# esp8266-01_carrier.net
KiCad netlist of a schematic drawn in EAGLE
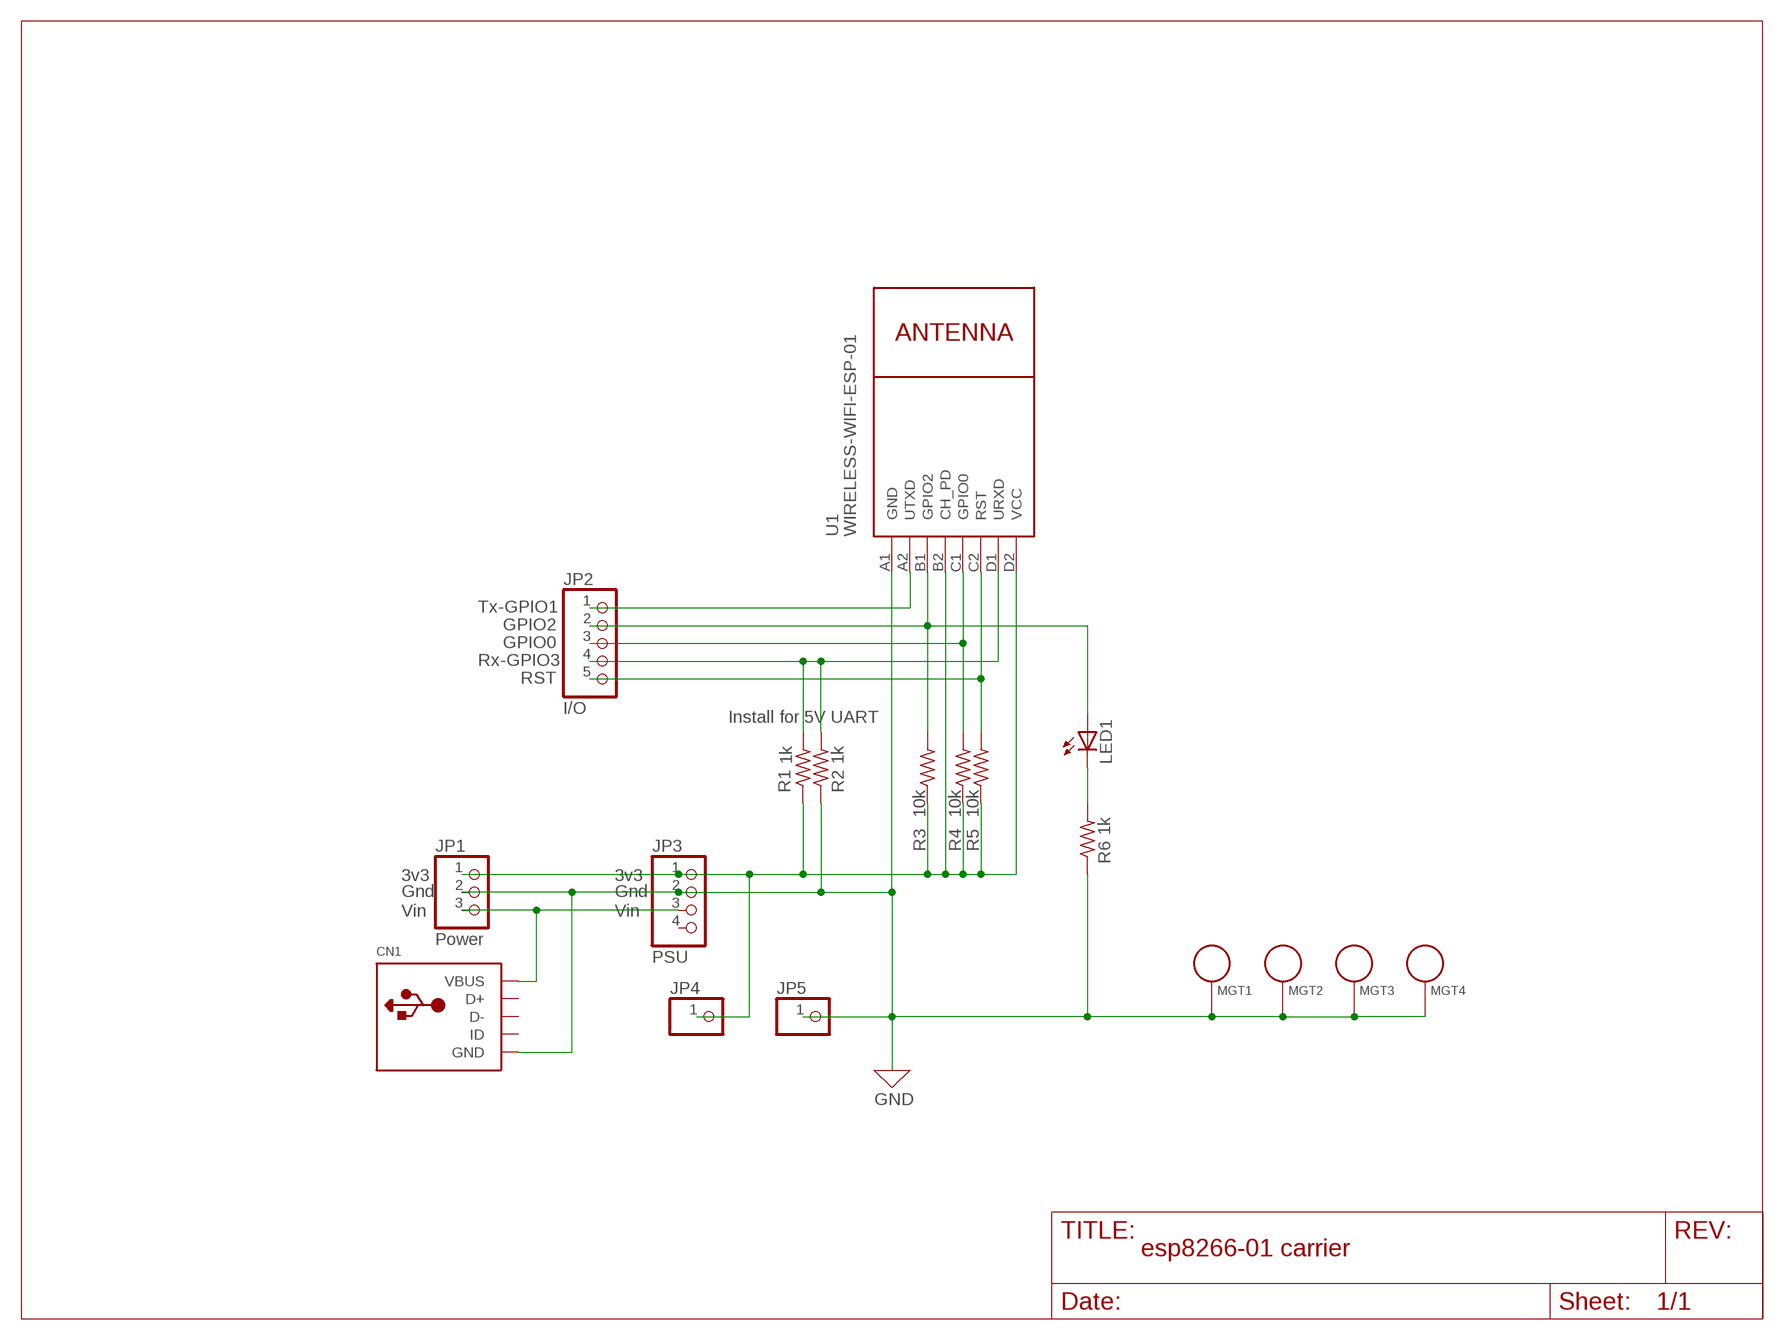
[diagram p0: schematic, sheet 1]

(export (version "E")
  (design (tool "Eeschema 10.0.6"))
  (components
    (comp (ref "CN1")
      (value "USBTHM")
      (footprint "eagle-import:USB-MINIB-THM")
      (libsource (lib "eagle-import") (part "USBTHM"))
    )
    (comp (ref "JP1")
      (value "Power")
      (footprint "eagle-import:1X03")
      (libsource (lib "eagle-import") (part "PINHD-1X3"))
    )
    (comp (ref "JP2")
      (value "I/O")
      (footprint "eagle-import:1X05")
      (libsource (lib "eagle-import") (part "PINHD-1X5"))
    )
    (comp (ref "JP3")
      (value "PSU")
      (footprint "eagle-import:1X04")
      (libsource (lib "eagle-import") (part "PINHD-1X4"))
    )
    (comp (ref "JP4")
      (value "PINHD-1X1")
      (footprint "eagle-import:1X01")
      (libsource (lib "eagle-import") (part "PINHD-1X1"))
    )
    (comp (ref "JP5")
      (value "PINHD-1X1")
      (footprint "eagle-import:1X01")
      (libsource (lib "eagle-import") (part "PINHD-1X1"))
    )
    (comp (ref "LED1")
      (value "LED5MM")
      (footprint "eagle-import:LED5MM")
      (libsource (lib "eagle-import") (part "LED5MM"))
    )
    (comp (ref "MGT1")
      (value "BEAGLEBONEBLACK_MOUNTING_HOLE")
      (footprint "eagle-import:BEAGLEBONEBLACK_MOUNTING_HOLE")
      (libsource (lib "eagle-import") (part "BEAGLEBONEBLACK_MOUNTING_HOLE"))
    )
    (comp (ref "MGT2")
      (value "BEAGLEBONEBLACK_MOUNTING_HOLE")
      (footprint "eagle-import:BEAGLEBONEBLACK_MOUNTING_HOLE")
      (libsource (lib "eagle-import") (part "BEAGLEBONEBLACK_MOUNTING_HOLE"))
    )
    (comp (ref "MGT3")
      (value "BEAGLEBONEBLACK_MOUNTING_HOLE")
      (footprint "eagle-import:BEAGLEBONEBLACK_MOUNTING_HOLE")
      (libsource (lib "eagle-import") (part "BEAGLEBONEBLACK_MOUNTING_HOLE"))
    )
    (comp (ref "MGT4")
      (value "BEAGLEBONEBLACK_MOUNTING_HOLE")
      (footprint "eagle-import:BEAGLEBONEBLACK_MOUNTING_HOLE")
      (libsource (lib "eagle-import") (part "BEAGLEBONEBLACK_MOUNTING_HOLE"))
    )
    (comp (ref "R1")
      (value "1k")
      (footprint "eagle-import:0207_10")
      (libsource (lib "eagle-import") (part "R-US_0207/10"))
    )
    (comp (ref "R2")
      (value "1k")
      (footprint "eagle-import:0207_10")
      (libsource (lib "eagle-import") (part "R-US_0207/10"))
    )
    (comp (ref "R3")
      (value "10k")
      (footprint "eagle-import:0207_10")
      (libsource (lib "eagle-import") (part "R-US_0207/10"))
    )
    (comp (ref "R4")
      (value "10k")
      (footprint "eagle-import:0207_10")
      (libsource (lib "eagle-import") (part "R-US_0207/10"))
    )
    (comp (ref "R5")
      (value "10k")
      (footprint "eagle-import:0207_10")
      (libsource (lib "eagle-import") (part "R-US_0207/10"))
    )
    (comp (ref "R6")
      (value "1k")
      (footprint "eagle-import:0207_10")
      (libsource (lib "eagle-import") (part "R-US_0207/10"))
    )
    (comp (ref "U1")
      (value "WIRELESS-WIFI-ESP-01")
      (footprint "eagle-import:WIRELESS-WIFI-ESP-01")
      (libsource (lib "eagle-import") (part "WIRELESS-WIFI-ESP-01"))
    )
  )
  (nets
    (net (code "1") (name "GND") (class "Default")
      (node (ref "CN1") (pin "GND") (pinfunction "GND_GND") (pintype "power_in"))
      (node (ref "JP1") (pin "2") (pinfunction "2_2") (pintype "passive"))
      (node (ref "JP3") (pin "2") (pinfunction "2_2") (pintype "passive"))
      (node (ref "JP5") (pin "1") (pinfunction "1_1") (pintype "passive"))
      (node (ref "MGT1") (pin "P$1") (pinfunction "P$1_P$1") (pintype "bidirectional"))
      (node (ref "MGT2") (pin "P$1") (pinfunction "P$1_P$1") (pintype "bidirectional"))
      (node (ref "MGT3") (pin "P$1") (pinfunction "P$1_P$1") (pintype "bidirectional"))
      (node (ref "MGT4") (pin "P$1") (pinfunction "P$1_P$1") (pintype "bidirectional"))
      (node (ref "R2") (pin "1") (pinfunction "1_1") (pintype "passive"))
      (node (ref "R6") (pin "1") (pinfunction "1_1") (pintype "passive"))
      (node (ref "U1") (pin "A1") (pinfunction "GND_A1") (pintype "power_in"))
    )
    (net (code "2") (name "Net-(CN1-PadVBUS)") (class "Default")
      (node (ref "CN1") (pin "VBUS") (pinfunction "VBUS_VBUS") (pintype "power_in"))
      (node (ref "JP1") (pin "3") (pinfunction "3_3") (pintype "passive"))
      (node (ref "JP3") (pin "3") (pinfunction "3_3") (pintype "passive"))
    )
    (net (code "3") (name "Net-(LED1-C)") (class "Default")
      (node (ref "LED1") (pin "K") (pinfunction "C_K") (pintype "passive"))
      (node (ref "R6") (pin "2") (pinfunction "2_2") (pintype "passive"))
    )
    (net (code "4") (name "Net-(U1-CH_PD)") (class "Default")
      (node (ref "JP1") (pin "1") (pinfunction "1_1") (pintype "passive"))
      (node (ref "JP3") (pin "1") (pinfunction "1_1") (pintype "passive"))
      (node (ref "JP4") (pin "1") (pinfunction "1_1") (pintype "passive"))
      (node (ref "R1") (pin "1") (pinfunction "1_1") (pintype "passive"))
      (node (ref "R3") (pin "1") (pinfunction "1_1") (pintype "passive"))
      (node (ref "R4") (pin "1") (pinfunction "1_1") (pintype "passive"))
      (node (ref "R5") (pin "1") (pinfunction "1_1") (pintype "passive"))
      (node (ref "U1") (pin "B2") (pinfunction "CH_PD_B2") (pintype "bidirectional"))
      (node (ref "U1") (pin "D2") (pinfunction "VCC_D2") (pintype "power_in"))
    )
    (net (code "5") (name "Net-(U1-GPIO0)") (class "Default")
      (node (ref "JP2") (pin "3") (pinfunction "3_3") (pintype "passive"))
      (node (ref "R4") (pin "2") (pinfunction "2_2") (pintype "passive"))
      (node (ref "U1") (pin "C1") (pinfunction "GPIO0_C1") (pintype "bidirectional"))
    )
    (net (code "6") (name "Net-(U1-GPIO2)") (class "Default")
      (node (ref "JP2") (pin "2") (pinfunction "2_2") (pintype "passive"))
      (node (ref "LED1") (pin "A") (pinfunction "A_A") (pintype "passive"))
      (node (ref "R3") (pin "2") (pinfunction "2_2") (pintype "passive"))
      (node (ref "U1") (pin "B1") (pinfunction "GPIO2_B1") (pintype "bidirectional"))
    )
    (net (code "7") (name "Net-(U1-RST)") (class "Default")
      (node (ref "JP2") (pin "5") (pinfunction "5_5") (pintype "passive"))
      (node (ref "R5") (pin "2") (pinfunction "2_2") (pintype "passive"))
      (node (ref "U1") (pin "C2") (pinfunction "RST_C2") (pintype "bidirectional"))
    )
    (net (code "8") (name "Net-(U1-URXD)") (class "Default")
      (node (ref "JP2") (pin "4") (pinfunction "4_4") (pintype "passive"))
      (node (ref "R1") (pin "2") (pinfunction "2_2") (pintype "passive"))
      (node (ref "R2") (pin "2") (pinfunction "2_2") (pintype "passive"))
      (node (ref "U1") (pin "D1") (pinfunction "URXD_D1") (pintype "bidirectional"))
    )
    (net (code "9") (name "Net-(U1-UTXD)") (class "Default")
      (node (ref "JP2") (pin "1") (pinfunction "1_1") (pintype "passive"))
      (node (ref "U1") (pin "A2") (pinfunction "UTXD_A2") (pintype "bidirectional"))
    )
    (net (code "10") (name "unconnected-(CN1-PadD+)") (class "Default")
      (node (ref "CN1") (pin "D+") (pinfunction "D+_D+") (pintype "bidirectional"))
    )
    (net (code "11") (name "unconnected-(CN1-PadD-)") (class "Default")
      (node (ref "CN1") (pin "D-") (pinfunction "D-_D-") (pintype "bidirectional"))
    )
    (net (code "12") (name "unconnected-(CN1-PadID)") (class "Default")
      (node (ref "CN1") (pin "ID") (pinfunction "ID_ID") (pintype "bidirectional"))
    )
    (net (code "13") (name "unconnected-(JP3-Pad4)") (class "Default")
      (node (ref "JP3") (pin "4") (pinfunction "4_4") (pintype "passive"))
    )
  )
)
